# M161XX.net
KiCad netlist of a schematic drawn in EAGLE
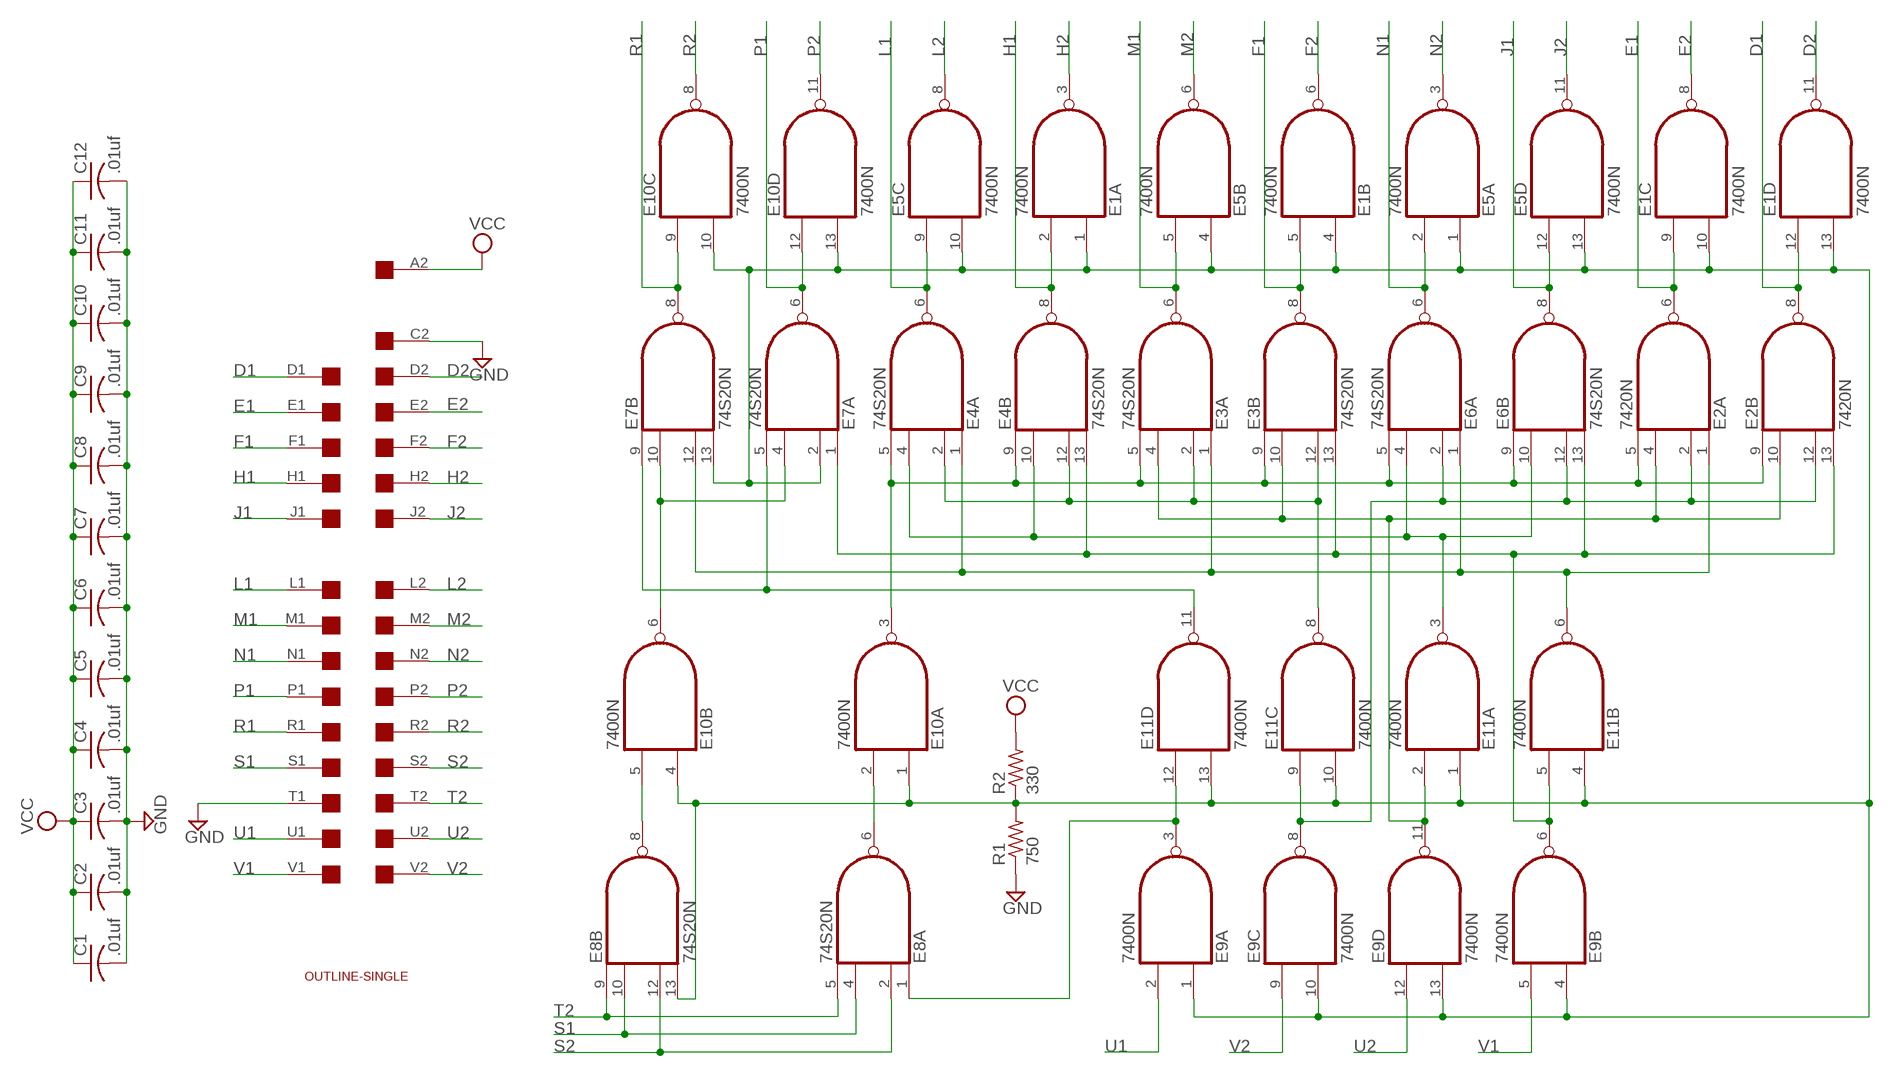
[diagram p0: schematic, sheet 1]

(export (version "E")
  (design (tool "Eeschema 10.0.6"))
  (components
    (comp (ref "C1")
      (value ".01uf")
      (footprint "eagle-import:C050-025X075")
      (libsource (lib "eagle-import") (part "C-US050-025X075"))
    )
    (comp (ref "C2")
      (value ".01uf")
      (footprint "eagle-import:C050-025X075")
      (libsource (lib "eagle-import") (part "C-US050-025X075"))
    )
    (comp (ref "C3")
      (value ".01uf")
      (footprint "eagle-import:C050-025X075")
      (libsource (lib "eagle-import") (part "C-US050-025X075"))
    )
    (comp (ref "C4")
      (value ".01uf")
      (footprint "eagle-import:C050-025X075")
      (libsource (lib "eagle-import") (part "C-US050-025X075"))
    )
    (comp (ref "C5")
      (value ".01uf")
      (footprint "eagle-import:C050-025X075")
      (libsource (lib "eagle-import") (part "C-US050-025X075"))
    )
    (comp (ref "C6")
      (value ".01uf")
      (footprint "eagle-import:C050-025X075")
      (libsource (lib "eagle-import") (part "C-US050-025X075"))
    )
    (comp (ref "C7")
      (value ".01uf")
      (footprint "eagle-import:C050-025X075")
      (libsource (lib "eagle-import") (part "C-US050-025X075"))
    )
    (comp (ref "C8")
      (value ".01uf")
      (footprint "eagle-import:C050-025X075")
      (libsource (lib "eagle-import") (part "C-US050-025X075"))
    )
    (comp (ref "C9")
      (value ".01uf")
      (footprint "eagle-import:C050-025X075")
      (libsource (lib "eagle-import") (part "C-US050-025X075"))
    )
    (comp (ref "C10")
      (value ".01uf")
      (footprint "eagle-import:C050-025X075")
      (libsource (lib "eagle-import") (part "C-US050-025X075"))
    )
    (comp (ref "C11")
      (value ".01uf")
      (footprint "eagle-import:C050-025X075")
      (libsource (lib "eagle-import") (part "C-US050-025X075"))
    )
    (comp (ref "C12")
      (value ".01uf")
      (footprint "eagle-import:C050-025X075")
      (libsource (lib "eagle-import") (part "C-US050-025X075"))
    )
    (comp (ref "E1")
      (value "7400N")
      (footprint "eagle-import:DIL14")
      (libsource (lib "eagle-import") (part "7400N"))
    )
    (comp (ref "E2")
      (value "7420N")
      (footprint "eagle-import:DIL14")
      (libsource (lib "eagle-import") (part "7420NS"))
    )
    (comp (ref "E3")
      (value "74S20N")
      (footprint "eagle-import:DIL14")
      (libsource (lib "eagle-import") (part "7420NS"))
    )
    (comp (ref "E4")
      (value "74S20N")
      (footprint "eagle-import:DIL14")
      (libsource (lib "eagle-import") (part "7420NS"))
    )
    (comp (ref "E5")
      (value "7400N")
      (footprint "eagle-import:DIL14")
      (libsource (lib "eagle-import") (part "7400N"))
    )
    (comp (ref "E6")
      (value "74S20N")
      (footprint "eagle-import:DIL14")
      (libsource (lib "eagle-import") (part "7420NS"))
    )
    (comp (ref "E7")
      (value "74S20N")
      (footprint "eagle-import:DIL14")
      (libsource (lib "eagle-import") (part "7420NS"))
    )
    (comp (ref "E8")
      (value "74S20N")
      (footprint "eagle-import:DIL14")
      (libsource (lib "eagle-import") (part "7420NS"))
    )
    (comp (ref "E9")
      (value "7400N")
      (footprint "eagle-import:DIL14")
      (libsource (lib "eagle-import") (part "7400N"))
    )
    (comp (ref "E10")
      (value "7400N")
      (footprint "eagle-import:DIL14")
      (libsource (lib "eagle-import") (part "7400N"))
    )
    (comp (ref "E11")
      (value "7400N")
      (footprint "eagle-import:DIL14")
      (libsource (lib "eagle-import") (part "7400N"))
    )
    (comp (ref "R1")
      (value "750")
      (footprint "eagle-import:0207_10")
      (libsource (lib "eagle-import") (part "R-US_0207/10"))
    )
    (comp (ref "R2")
      (value "330")
      (footprint "eagle-import:0207_10")
      (libsource (lib "eagle-import") (part "R-US_0207/10"))
    )
    (comp (ref "U$1")
      (value "OUTLINE-SINGLE")
      (footprint "eagle-import:SINGLE")
      (libsource (lib "eagle-import") (part "OUTLINE-SINGLE"))
    )
    (comp (ref "U$4")
      (value "SINGLE")
      (footprint "eagle-import:EDGE-CON2")
      (libsource (lib "eagle-import") (part "SINGLE"))
    )
  )
  (nets
    (net (code "1") (name "/D1") (class "Default")
      (node (ref "E1") (pin "12") (pinfunction "I0_12") (pintype "input"))
      (node (ref "E2") (pin "8") (pinfunction "O_8") (pintype "output"))
      (node (ref "U$4") (pin "D1") (pinfunction "1_D1") (pintype "bidirectional"))
    )
    (net (code "2") (name "/D2") (class "Default")
      (node (ref "E1") (pin "11") (pinfunction "O_11") (pintype "output"))
      (node (ref "U$4") (pin "D2") (pinfunction "1_D2") (pintype "bidirectional"))
    )
    (net (code "3") (name "/E1") (class "Default")
      (node (ref "E1") (pin "9") (pinfunction "I0_9") (pintype "input"))
      (node (ref "E2") (pin "6") (pinfunction "O_6") (pintype "output"))
      (node (ref "U$4") (pin "E1") (pinfunction "1_E1") (pintype "bidirectional"))
    )
    (net (code "4") (name "/E2") (class "Default")
      (node (ref "E1") (pin "8") (pinfunction "O_8") (pintype "output"))
      (node (ref "U$4") (pin "E2") (pinfunction "1_E2") (pintype "bidirectional"))
    )
    (net (code "5") (name "/F1") (class "Default")
      (node (ref "E1") (pin "5") (pinfunction "I1_5") (pintype "input"))
      (node (ref "E3") (pin "8") (pinfunction "O_8") (pintype "output"))
      (node (ref "U$4") (pin "F1") (pinfunction "1_F1") (pintype "bidirectional"))
    )
    (net (code "6") (name "/F2") (class "Default")
      (node (ref "E1") (pin "6") (pinfunction "O_6") (pintype "output"))
      (node (ref "U$4") (pin "F2") (pinfunction "1_F2") (pintype "bidirectional"))
    )
    (net (code "7") (name "/H1") (class "Default")
      (node (ref "E1") (pin "2") (pinfunction "I1_2") (pintype "input"))
      (node (ref "E4") (pin "8") (pinfunction "O_8") (pintype "output"))
      (node (ref "U$4") (pin "H1") (pinfunction "1_H1") (pintype "bidirectional"))
    )
    (net (code "8") (name "/H2") (class "Default")
      (node (ref "E1") (pin "3") (pinfunction "O_3") (pintype "output"))
      (node (ref "U$4") (pin "H2") (pinfunction "1_H2") (pintype "bidirectional"))
    )
    (net (code "9") (name "/J1") (class "Default")
      (node (ref "E5") (pin "12") (pinfunction "I0_12") (pintype "input"))
      (node (ref "E6") (pin "8") (pinfunction "O_8") (pintype "output"))
      (node (ref "U$4") (pin "J1") (pinfunction "1_J1") (pintype "bidirectional"))
    )
    (net (code "10") (name "/J2") (class "Default")
      (node (ref "E5") (pin "11") (pinfunction "O_11") (pintype "output"))
      (node (ref "U$4") (pin "J2") (pinfunction "1_J2") (pintype "bidirectional"))
    )
    (net (code "11") (name "/L1") (class "Default")
      (node (ref "E4") (pin "6") (pinfunction "O_6") (pintype "output"))
      (node (ref "E5") (pin "9") (pinfunction "I0_9") (pintype "input"))
      (node (ref "U$4") (pin "L1") (pinfunction "1_L1") (pintype "bidirectional"))
    )
    (net (code "12") (name "/L2") (class "Default")
      (node (ref "E5") (pin "8") (pinfunction "O_8") (pintype "output"))
      (node (ref "U$4") (pin "L2") (pinfunction "1_L2") (pintype "bidirectional"))
    )
    (net (code "13") (name "/M1") (class "Default")
      (node (ref "E3") (pin "6") (pinfunction "O_6") (pintype "output"))
      (node (ref "E5") (pin "5") (pinfunction "I1_5") (pintype "input"))
      (node (ref "U$4") (pin "M1") (pinfunction "1_M1") (pintype "bidirectional"))
    )
    (net (code "14") (name "/M2") (class "Default")
      (node (ref "E5") (pin "6") (pinfunction "O_6") (pintype "output"))
      (node (ref "U$4") (pin "M2") (pinfunction "1_M2") (pintype "bidirectional"))
    )
    (net (code "15") (name "/N1") (class "Default")
      (node (ref "E5") (pin "2") (pinfunction "I1_2") (pintype "input"))
      (node (ref "E6") (pin "6") (pinfunction "O_6") (pintype "output"))
      (node (ref "U$4") (pin "N1") (pinfunction "1_N1") (pintype "bidirectional"))
    )
    (net (code "16") (name "/N2") (class "Default")
      (node (ref "E5") (pin "3") (pinfunction "O_3") (pintype "output"))
      (node (ref "U$4") (pin "N2") (pinfunction "1_N2") (pintype "bidirectional"))
    )
    (net (code "17") (name "/P1") (class "Default")
      (node (ref "E10") (pin "12") (pinfunction "I0_12") (pintype "input"))
      (node (ref "E7") (pin "6") (pinfunction "O_6") (pintype "output"))
      (node (ref "U$4") (pin "P1") (pinfunction "1_P1") (pintype "bidirectional"))
    )
    (net (code "18") (name "/P2") (class "Default")
      (node (ref "E10") (pin "11") (pinfunction "O_11") (pintype "output"))
      (node (ref "U$4") (pin "P2") (pinfunction "1_P2") (pintype "bidirectional"))
    )
    (net (code "19") (name "/R1") (class "Default")
      (node (ref "E10") (pin "9") (pinfunction "I0_9") (pintype "input"))
      (node (ref "E7") (pin "8") (pinfunction "O_8") (pintype "output"))
      (node (ref "U$4") (pin "R1") (pinfunction "1_R1") (pintype "bidirectional"))
    )
    (net (code "20") (name "/R2") (class "Default")
      (node (ref "E10") (pin "8") (pinfunction "O_8") (pintype "output"))
      (node (ref "U$4") (pin "R2") (pinfunction "1_R2") (pintype "bidirectional"))
    )
    (net (code "21") (name "/S1") (class "Default")
      (node (ref "E8") (pin "10") (pinfunction "I1_10") (pintype "input"))
      (node (ref "E8") (pin "4") (pinfunction "I2_4") (pintype "input"))
      (node (ref "U$4") (pin "S1") (pinfunction "1_S1") (pintype "bidirectional"))
    )
    (net (code "22") (name "/S2") (class "Default")
      (node (ref "E8") (pin "12") (pinfunction "I2_12") (pintype "input"))
      (node (ref "E8") (pin "2") (pinfunction "I1_2") (pintype "input"))
      (node (ref "U$4") (pin "S2") (pinfunction "1_S2") (pintype "bidirectional"))
    )
    (net (code "23") (name "/T2") (class "Default")
      (node (ref "E8") (pin "5") (pinfunction "I3_5") (pintype "input"))
      (node (ref "E8") (pin "9") (pinfunction "I0_9") (pintype "input"))
      (node (ref "U$4") (pin "T2") (pinfunction "1_T2") (pintype "bidirectional"))
    )
    (net (code "24") (name "/U1") (class "Default")
      (node (ref "E9") (pin "2") (pinfunction "I1_2") (pintype "input"))
      (node (ref "U$4") (pin "U1") (pinfunction "1_U1") (pintype "bidirectional"))
    )
    (net (code "25") (name "/U2") (class "Default")
      (node (ref "E9") (pin "12") (pinfunction "I0_12") (pintype "input"))
      (node (ref "U$4") (pin "U2") (pinfunction "1_U2") (pintype "bidirectional"))
    )
    (net (code "26") (name "/V1") (class "Default")
      (node (ref "E9") (pin "5") (pinfunction "I1_5") (pintype "input"))
      (node (ref "U$4") (pin "V1") (pinfunction "1_V1") (pintype "bidirectional"))
    )
    (net (code "27") (name "/V2") (class "Default")
      (node (ref "E9") (pin "9") (pinfunction "I0_9") (pintype "input"))
      (node (ref "U$4") (pin "V2") (pinfunction "1_V2") (pintype "bidirectional"))
    )
    (net (code "28") (name "GND") (class "Default")
      (node (ref "C1") (pin "2") (pinfunction "2_2") (pintype "passive"))
      (node (ref "C10") (pin "2") (pinfunction "2_2") (pintype "passive"))
      (node (ref "C11") (pin "2") (pinfunction "2_2") (pintype "passive"))
      (node (ref "C12") (pin "2") (pinfunction "2_2") (pintype "passive"))
      (node (ref "C2") (pin "2") (pinfunction "2_2") (pintype "passive"))
      (node (ref "C3") (pin "2") (pinfunction "2_2") (pintype "passive"))
      (node (ref "C4") (pin "2") (pinfunction "2_2") (pintype "passive"))
      (node (ref "C5") (pin "2") (pinfunction "2_2") (pintype "passive"))
      (node (ref "C6") (pin "2") (pinfunction "2_2") (pintype "passive"))
      (node (ref "C7") (pin "2") (pinfunction "2_2") (pintype "passive"))
      (node (ref "C8") (pin "2") (pinfunction "2_2") (pintype "passive"))
      (node (ref "C9") (pin "2") (pinfunction "2_2") (pintype "passive"))
      (node (ref "R1") (pin "1") (pinfunction "1_1") (pintype "passive"))
      (node (ref "U$4") (pin "C2") (pinfunction "1_C2") (pintype "bidirectional"))
      (node (ref "U$4") (pin "T1") (pinfunction "1_T1") (pintype "bidirectional"))
    )
    (net (code "29") (name "Net-(E10A-I0)") (class "Default")
      (node (ref "E1") (pin "1") (pinfunction "I0_1") (pintype "input"))
      (node (ref "E1") (pin "10") (pinfunction "I1_10") (pintype "input"))
      (node (ref "E1") (pin "13") (pinfunction "I1_13") (pintype "input"))
      (node (ref "E1") (pin "4") (pinfunction "I0_4") (pintype "input"))
      (node (ref "E10") (pin "1") (pinfunction "I0_1") (pintype "input"))
      (node (ref "E10") (pin "10") (pinfunction "I1_10") (pintype "input"))
      (node (ref "E10") (pin "13") (pinfunction "I1_13") (pintype "input"))
      (node (ref "E10") (pin "4") (pinfunction "I0_4") (pintype "input"))
      (node (ref "E11") (pin "1") (pinfunction "I0_1") (pintype "input"))
      (node (ref "E11") (pin "10") (pinfunction "I1_10") (pintype "input"))
      (node (ref "E11") (pin "13") (pinfunction "I1_13") (pintype "input"))
      (node (ref "E11") (pin "4") (pinfunction "I0_4") (pintype "input"))
      (node (ref "E5") (pin "1") (pinfunction "I0_1") (pintype "input"))
      (node (ref "E5") (pin "10") (pinfunction "I1_10") (pintype "input"))
      (node (ref "E5") (pin "13") (pinfunction "I1_13") (pintype "input"))
      (node (ref "E5") (pin "4") (pinfunction "I0_4") (pintype "input"))
      (node (ref "E7") (pin "13") (pinfunction "I3_13") (pintype "input"))
      (node (ref "E7") (pin "2") (pinfunction "I1_2") (pintype "input"))
      (node (ref "E8") (pin "13") (pinfunction "I3_13") (pintype "input"))
      (node (ref "E9") (pin "1") (pinfunction "I0_1") (pintype "input"))
      (node (ref "E9") (pin "10") (pinfunction "I1_10") (pintype "input"))
      (node (ref "E9") (pin "13") (pinfunction "I1_13") (pintype "input"))
      (node (ref "E9") (pin "4") (pinfunction "I0_4") (pintype "input"))
      (node (ref "R1") (pin "2") (pinfunction "2_2") (pintype "passive"))
      (node (ref "R2") (pin "1") (pinfunction "1_1") (pintype "passive"))
    )
    (net (code "30") (name "Net-(E10A-I1)") (class "Default")
      (node (ref "E10") (pin "2") (pinfunction "I1_2") (pintype "input"))
      (node (ref "E8") (pin "6") (pinfunction "O_6") (pintype "output"))
    )
    (net (code "31") (name "Net-(E10A-O)") (class "Default")
      (node (ref "E10") (pin "3") (pinfunction "O_3") (pintype "output"))
      (node (ref "E2") (pin "5") (pinfunction "I3_5") (pintype "input"))
      (node (ref "E2") (pin "9") (pinfunction "I0_9") (pintype "input"))
      (node (ref "E3") (pin "5") (pinfunction "I3_5") (pintype "input"))
      (node (ref "E3") (pin "9") (pinfunction "I0_9") (pintype "input"))
      (node (ref "E4") (pin "5") (pinfunction "I3_5") (pintype "input"))
      (node (ref "E4") (pin "9") (pinfunction "I0_9") (pintype "input"))
      (node (ref "E6") (pin "5") (pinfunction "I3_5") (pintype "input"))
      (node (ref "E6") (pin "9") (pinfunction "I0_9") (pintype "input"))
    )
    (net (code "32") (name "Net-(E10B-I1)") (class "Default")
      (node (ref "E10") (pin "5") (pinfunction "I1_5") (pintype "input"))
      (node (ref "E8") (pin "8") (pinfunction "O_8") (pintype "output"))
    )
    (net (code "33") (name "Net-(E10B-O)") (class "Default")
      (node (ref "E10") (pin "6") (pinfunction "O_6") (pintype "output"))
      (node (ref "E7") (pin "10") (pinfunction "I1_10") (pintype "input"))
      (node (ref "E7") (pin "4") (pinfunction "I2_4") (pintype "input"))
    )
    (net (code "34") (name "Net-(E11A-I1)") (class "Default")
      (node (ref "E11") (pin "2") (pinfunction "I1_2") (pintype "input"))
      (node (ref "E2") (pin "10") (pinfunction "I1_10") (pintype "input"))
      (node (ref "E2") (pin "4") (pinfunction "I2_4") (pintype "input"))
      (node (ref "E3") (pin "10") (pinfunction "I1_10") (pintype "input"))
      (node (ref "E3") (pin "4") (pinfunction "I2_4") (pintype "input"))
      (node (ref "E9") (pin "11") (pinfunction "O_11") (pintype "output"))
    )
    (net (code "35") (name "Net-(E11A-O)") (class "Default")
      (node (ref "E11") (pin "3") (pinfunction "O_3") (pintype "output"))
      (node (ref "E4") (pin "10") (pinfunction "I1_10") (pintype "input"))
      (node (ref "E4") (pin "4") (pinfunction "I2_4") (pintype "input"))
      (node (ref "E6") (pin "10") (pinfunction "I1_10") (pintype "input"))
      (node (ref "E6") (pin "4") (pinfunction "I2_4") (pintype "input"))
    )
    (net (code "36") (name "Net-(E11B-I1)") (class "Default")
      (node (ref "E11") (pin "5") (pinfunction "I1_5") (pintype "input"))
      (node (ref "E2") (pin "13") (pinfunction "I3_13") (pintype "input"))
      (node (ref "E3") (pin "13") (pinfunction "I3_13") (pintype "input"))
      (node (ref "E4") (pin "13") (pinfunction "I3_13") (pintype "input"))
      (node (ref "E6") (pin "13") (pinfunction "I3_13") (pintype "input"))
      (node (ref "E7") (pin "1") (pinfunction "I0_1") (pintype "input"))
      (node (ref "E9") (pin "6") (pinfunction "O_6") (pintype "output"))
    )
    (net (code "37") (name "Net-(E11B-O)") (class "Default")
      (node (ref "E11") (pin "6") (pinfunction "O_6") (pintype "output"))
      (node (ref "E2") (pin "1") (pinfunction "I0_1") (pintype "input"))
      (node (ref "E3") (pin "1") (pinfunction "I0_1") (pintype "input"))
      (node (ref "E4") (pin "1") (pinfunction "I0_1") (pintype "input"))
      (node (ref "E6") (pin "1") (pinfunction "I0_1") (pintype "input"))
      (node (ref "E7") (pin "12") (pinfunction "I2_12") (pintype "input"))
    )
    (net (code "38") (name "Net-(E11C-I0)") (class "Default")
      (node (ref "E11") (pin "9") (pinfunction "I0_9") (pintype "input"))
      (node (ref "E2") (pin "12") (pinfunction "I2_12") (pintype "input"))
      (node (ref "E2") (pin "2") (pinfunction "I1_2") (pintype "input"))
      (node (ref "E6") (pin "12") (pinfunction "I2_12") (pintype "input"))
      (node (ref "E6") (pin "2") (pinfunction "I1_2") (pintype "input"))
      (node (ref "E9") (pin "8") (pinfunction "O_8") (pintype "output"))
    )
    (net (code "39") (name "Net-(E11C-O)") (class "Default")
      (node (ref "E11") (pin "8") (pinfunction "O_8") (pintype "output"))
      (node (ref "E3") (pin "12") (pinfunction "I2_12") (pintype "input"))
      (node (ref "E3") (pin "2") (pinfunction "I1_2") (pintype "input"))
      (node (ref "E4") (pin "12") (pinfunction "I2_12") (pintype "input"))
      (node (ref "E4") (pin "2") (pinfunction "I1_2") (pintype "input"))
    )
    (net (code "40") (name "Net-(E11D-I0)") (class "Default")
      (node (ref "E11") (pin "12") (pinfunction "I0_12") (pintype "input"))
      (node (ref "E8") (pin "1") (pinfunction "I0_1") (pintype "input"))
      (node (ref "E9") (pin "3") (pinfunction "O_3") (pintype "output"))
    )
    (net (code "41") (name "Net-(E11D-O)") (class "Default")
      (node (ref "E11") (pin "11") (pinfunction "O_11") (pintype "output"))
      (node (ref "E7") (pin "5") (pinfunction "I3_5") (pintype "input"))
      (node (ref "E7") (pin "9") (pinfunction "I0_9") (pintype "input"))
    )
    (net (code "42") (name "VCC") (class "Default")
      (node (ref "C1") (pin "1") (pinfunction "1_1") (pintype "passive"))
      (node (ref "C10") (pin "1") (pinfunction "1_1") (pintype "passive"))
      (node (ref "C11") (pin "1") (pinfunction "1_1") (pintype "passive"))
      (node (ref "C12") (pin "1") (pinfunction "1_1") (pintype "passive"))
      (node (ref "C2") (pin "1") (pinfunction "1_1") (pintype "passive"))
      (node (ref "C3") (pin "1") (pinfunction "1_1") (pintype "passive"))
      (node (ref "C4") (pin "1") (pinfunction "1_1") (pintype "passive"))
      (node (ref "C5") (pin "1") (pinfunction "1_1") (pintype "passive"))
      (node (ref "C6") (pin "1") (pinfunction "1_1") (pintype "passive"))
      (node (ref "C7") (pin "1") (pinfunction "1_1") (pintype "passive"))
      (node (ref "C8") (pin "1") (pinfunction "1_1") (pintype "passive"))
      (node (ref "C9") (pin "1") (pinfunction "1_1") (pintype "passive"))
      (node (ref "R2") (pin "2") (pinfunction "2_2") (pintype "passive"))
      (node (ref "U$4") (pin "A2") (pinfunction "1_A2") (pintype "bidirectional"))
    )
  )
)
